# design.net
KiCad netlist of a schematic drawn in Altium Designer
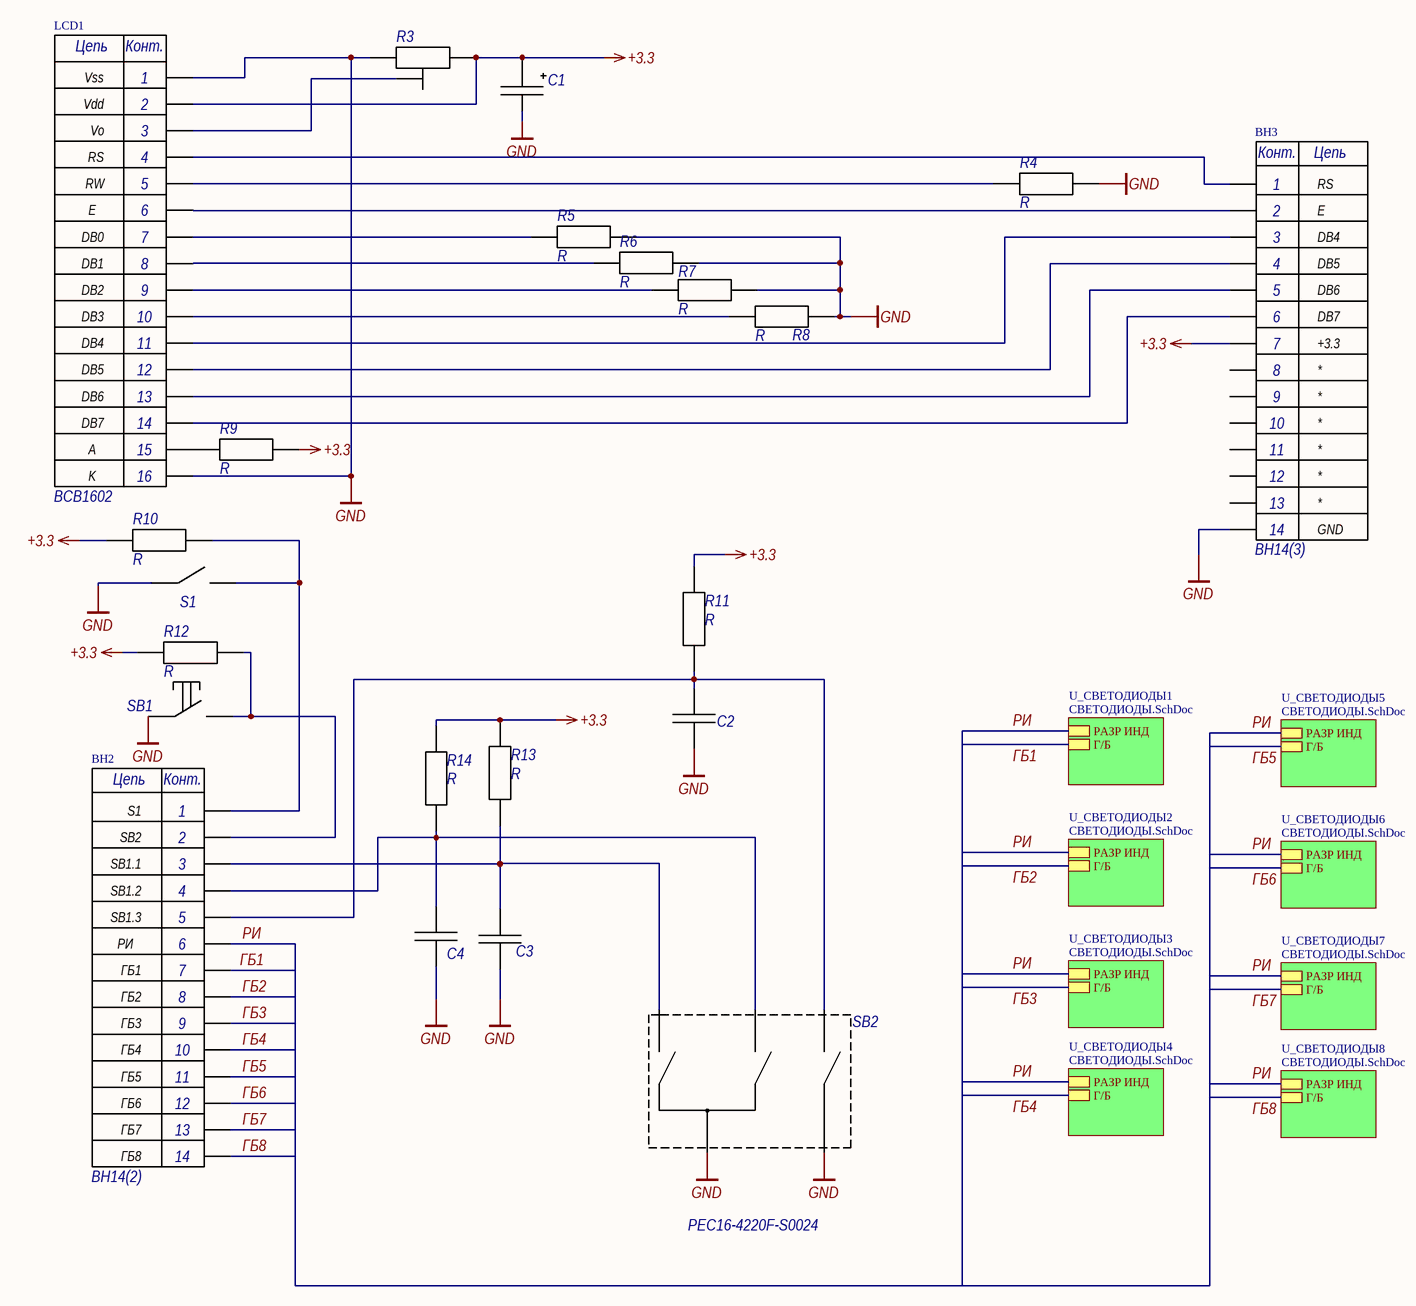
[diagram p0: управление+отладка.SchDoc]

(export (version "E")
  (design (tool "Eeschema 10.0.6"))
  (components
    (comp (ref "BH2")
      (value "BH14(2)")
      (footprint "BH-14 (DS1013-14S) (IDC-14MS)")
      (libsource (lib "UGO") (part "BH14(2)"))
    )
    (comp (ref "BH3")
      (value "BH14(3)")
      (footprint "BH-14 (DS1013-14S) (IDC-14MS)")
      (libsource (lib "UGO") (part "BH14(3)"))
    )
    (comp (ref "C1") (value "C(AlEL)") (footprint "C(AlEL)") (libsource (lib "UGO") (part "C(AlEL)")))
    (comp (ref "C2")
      (value "C(ceramic)")
      (footprint "C(ceramic)")
      (libsource (lib "UGO") (part "C(ceramic)"))
    )
    (comp (ref "C3")
      (value "C(ceramic)")
      (footprint "C(ceramic)")
      (libsource (lib "UGO") (part "C(ceramic)"))
    )
    (comp (ref "C4")
      (value "C(ceramic)")
      (footprint "C(ceramic)")
      (libsource (lib "UGO") (part "C(ceramic)"))
    )
    (comp (ref "LCD1") (value "BCB1602") (footprint "BCB1602") (libsource (lib "UGO") (part "BCB1602")))
    (comp (ref "R3") (value "Comment") (footprint "R(подстр)") (libsource (lib "UGO") (part "R(подстр)")))
    (comp (ref "R4") (value "R") (footprint "R") (libsource (lib "UGO") (part "R")))
    (comp (ref "R5") (value "R") (footprint "R") (libsource (lib "UGO") (part "R")))
    (comp (ref "R6") (value "R") (footprint "R") (libsource (lib "UGO") (part "R")))
    (comp (ref "R7") (value "R") (footprint "R") (libsource (lib "UGO") (part "R")))
    (comp (ref "R8") (value "R") (footprint "R") (libsource (lib "UGO") (part "R")))
    (comp (ref "R9") (value "R") (footprint "R") (libsource (lib "UGO") (part "R")))
    (comp (ref "R10") (value "R") (footprint "R") (libsource (lib "UGO") (part "R")))
    (comp (ref "R11") (value "R") (footprint "R") (libsource (lib "") (part "R_1")))
    (comp (ref "R12") (value "R") (footprint "R") (libsource (lib "UGO") (part "R")))
    (comp (ref "R13") (value "R") (footprint "R") (libsource (lib "") (part "R_1")))
    (comp (ref "R14") (value "R") (footprint "R") (libsource (lib "") (part "R_1")))
    (comp (ref "S1") (value "(?)тумблер") (footprint "MTS-2") (libsource (lib "UGO") (part "(?)тумблер")))
    (comp (ref "SB1") (value "ПУСК") (footprint "кнопка") (libsource (lib "UGO") (part "кнопка")))
    (comp (ref "SB2")
      (value "PEC16-4220F-S0024")
      (footprint "PEC16-4220F-S0024")
      (libsource (lib "UGO") (part "PEC16-4220F-S0024"))
    )
  )
  (nets
    (net (code "1") (name "+3.3") (class "Default")
      (node (ref "BH3") (pin "7") (pinfunction "+3.3_7") (pintype "passive"))
      (node (ref "C1") (pin "1") (pintype "passive"))
      (node (ref "LCD1") (pin "2") (pinfunction "Vdd_2") (pintype "passive"))
      (node (ref "R10") (pin "1") (pintype "passive"))
      (node (ref "R11") (pin "2") (pintype "passive"))
      (node (ref "R12") (pin "1") (pintype "passive"))
      (node (ref "R13") (pin "2") (pintype "passive"))
      (node (ref "R14") (pin "2") (pintype "passive"))
      (node (ref "R3") (pin "1") (pintype "passive"))
      (node (ref "R9") (pin "2") (pintype "passive"))
    )
    (net (code "2") (name "/ГБ1") (class "Default")
      (node (ref "BH2") (pin "7") (pinfunction "ГБ1_7") (pintype "passive"))
    )
    (net (code "3") (name "/ГБ2") (class "Default")
      (node (ref "BH2") (pin "8") (pinfunction "ГБ2_8") (pintype "passive"))
    )
    (net (code "4") (name "/ГБ3") (class "Default")
      (node (ref "BH2") (pin "9") (pinfunction "ГБ3_9") (pintype "passive"))
    )
    (net (code "5") (name "/ГБ4") (class "Default")
      (node (ref "BH2") (pin "10") (pinfunction "ГБ4_10") (pintype "passive"))
    )
    (net (code "6") (name "/ГБ5") (class "Default")
      (node (ref "BH2") (pin "11") (pinfunction "ГБ5_11") (pintype "passive"))
    )
    (net (code "7") (name "/ГБ6") (class "Default")
      (node (ref "BH2") (pin "12") (pinfunction "ГБ6_12") (pintype "passive"))
    )
    (net (code "8") (name "/ГБ7") (class "Default")
      (node (ref "BH2") (pin "13") (pinfunction "ГБ7_13") (pintype "passive"))
    )
    (net (code "9") (name "/ГБ8") (class "Default")
      (node (ref "BH2") (pin "14") (pinfunction "ГБ8_14") (pintype "passive"))
    )
    (net (code "10") (name "/РИ") (class "Default")
      (node (ref "BH2") (pin "6") (pinfunction "РИ_6") (pintype "passive"))
    )
    (net (code "11") (name "GND") (class "Default")
      (node (ref "BH3") (pin "14") (pinfunction "GND_14") (pintype "passive"))
      (node (ref "C1") (pin "2") (pintype "passive"))
      (node (ref "C2") (pin "1") (pintype "passive"))
      (node (ref "C3") (pin "1") (pintype "passive"))
      (node (ref "C4") (pin "1") (pintype "passive"))
      (node (ref "LCD1") (pin "1") (pinfunction "Vss_1") (pintype "passive"))
      (node (ref "LCD1") (pin "16") (pinfunction "K_16") (pintype "passive"))
      (node (ref "R3") (pin "2") (pintype "passive"))
      (node (ref "R4") (pin "2") (pintype "passive"))
      (node (ref "R5") (pin "2") (pintype "passive"))
      (node (ref "R6") (pin "2") (pintype "passive"))
      (node (ref "R7") (pin "2") (pintype "passive"))
      (node (ref "R8") (pin "2") (pintype "passive"))
      (node (ref "S1") (pin "1") (pintype "passive"))
      (node (ref "SB1") (pin "1") (pintype "passive"))
      (node (ref "SB2") (pin "2") (pintype "passive"))
      (node (ref "SB2") (pin "4") (pintype "passive"))
    )
    (net (code "12") (name "Net-(BH2-S1)") (class "Default")
      (node (ref "BH2") (pin "1") (pinfunction "S1_1") (pintype "passive"))
      (node (ref "R10") (pin "2") (pintype "passive"))
      (node (ref "S1") (pin "2") (pintype "passive"))
    )
    (net (code "13") (name "Net-(BH2-SB1.1)") (class "Default")
      (node (ref "BH2") (pin "3") (pinfunction "SB1.1_3") (pintype "passive"))
      (node (ref "C3") (pin "2") (pintype "passive"))
      (node (ref "R13") (pin "1") (pintype "passive"))
      (node (ref "SB2") (pin "1") (pintype "passive"))
    )
    (net (code "14") (name "Net-(BH2-SB1.2)") (class "Default")
      (node (ref "BH2") (pin "4") (pinfunction "SB1.2_4") (pintype "passive"))
      (node (ref "C4") (pin "2") (pintype "passive"))
      (node (ref "R14") (pin "1") (pintype "passive"))
      (node (ref "SB2") (pin "3") (pintype "passive"))
    )
    (net (code "15") (name "Net-(BH2-SB1.3)") (class "Default")
      (node (ref "BH2") (pin "5") (pinfunction "SB1.3_5") (pintype "passive"))
      (node (ref "C2") (pin "2") (pintype "passive"))
      (node (ref "R11") (pin "1") (pintype "passive"))
      (node (ref "SB2") (pin "5") (pintype "passive"))
    )
    (net (code "16") (name "Net-(BH2-SB2)") (class "Default")
      (node (ref "BH2") (pin "2") (pinfunction "SB2_2") (pintype "passive"))
      (node (ref "R12") (pin "2") (pintype "passive"))
      (node (ref "SB1") (pin "2") (pintype "passive"))
    )
    (net (code "17") (name "Net-(BH3-DB4)") (class "Default")
      (node (ref "BH3") (pin "3") (pinfunction "DB4_3") (pintype "passive"))
      (node (ref "LCD1") (pin "11") (pinfunction "DB4_11") (pintype "passive"))
    )
    (net (code "18") (name "Net-(BH3-DB5)") (class "Default")
      (node (ref "BH3") (pin "4") (pinfunction "DB5_4") (pintype "passive"))
      (node (ref "LCD1") (pin "12") (pinfunction "DB5_12") (pintype "passive"))
    )
    (net (code "19") (name "Net-(BH3-DB6)") (class "Default")
      (node (ref "BH3") (pin "5") (pinfunction "DB6_5") (pintype "passive"))
      (node (ref "LCD1") (pin "13") (pinfunction "DB6_13") (pintype "passive"))
    )
    (net (code "20") (name "Net-(BH3-DB7)") (class "Default")
      (node (ref "BH3") (pin "6") (pinfunction "DB7_6") (pintype "passive"))
      (node (ref "LCD1") (pin "14") (pinfunction "DB7_14") (pintype "passive"))
    )
    (net (code "21") (name "Net-(BH3-E)") (class "Default")
      (node (ref "BH3") (pin "2") (pinfunction "E_2") (pintype "passive"))
      (node (ref "LCD1") (pin "6") (pinfunction "E_6") (pintype "passive"))
    )
    (net (code "22") (name "Net-(BH3-RS)") (class "Default")
      (node (ref "BH3") (pin "1") (pinfunction "RS_1") (pintype "passive"))
      (node (ref "LCD1") (pin "4") (pinfunction "RS_4") (pintype "passive"))
    )
    (net (code "23") (name "Net-(LCD1-A)") (class "Default")
      (node (ref "LCD1") (pin "15") (pinfunction "A_15") (pintype "passive"))
      (node (ref "R9") (pin "1") (pintype "passive"))
    )
    (net (code "24") (name "Net-(LCD1-DB0)") (class "Default")
      (node (ref "LCD1") (pin "7") (pinfunction "DB0_7") (pintype "passive"))
      (node (ref "R5") (pin "1") (pintype "passive"))
    )
    (net (code "25") (name "Net-(LCD1-DB1)") (class "Default")
      (node (ref "LCD1") (pin "8") (pinfunction "DB1_8") (pintype "passive"))
      (node (ref "R6") (pin "1") (pintype "passive"))
    )
    (net (code "26") (name "Net-(LCD1-DB2)") (class "Default")
      (node (ref "LCD1") (pin "9") (pinfunction "DB2_9") (pintype "passive"))
      (node (ref "R7") (pin "1") (pintype "passive"))
    )
    (net (code "27") (name "Net-(LCD1-DB3)") (class "Default")
      (node (ref "LCD1") (pin "10") (pinfunction "DB3_10") (pintype "passive"))
      (node (ref "R8") (pin "1") (pintype "passive"))
    )
    (net (code "28") (name "Net-(LCD1-RW)") (class "Default")
      (node (ref "LCD1") (pin "5") (pinfunction "RW_5") (pintype "passive"))
      (node (ref "R4") (pin "1") (pintype "passive"))
    )
    (net (code "29") (name "Net-(LCD1-Vo)") (class "Default")
      (node (ref "LCD1") (pin "3") (pinfunction "Vo_3") (pintype "passive"))
      (node (ref "R3") (pin "3") (pintype "passive"))
    )
    (net (code "30") (name "unconnected-(BH3-*-Pad8)") (class "Default")
      (node (ref "BH3") (pin "8") (pinfunction "*_8") (pintype "passive"))
    )
    (net (code "31") (name "unconnected-(BH3-*-Pad9)") (class "Default")
      (node (ref "BH3") (pin "9") (pinfunction "*_9") (pintype "passive"))
    )
    (net (code "32") (name "unconnected-(BH3-*-Pad10)") (class "Default")
      (node (ref "BH3") (pin "10") (pinfunction "*_10") (pintype "passive"))
    )
    (net (code "33") (name "unconnected-(BH3-*-Pad11)") (class "Default")
      (node (ref "BH3") (pin "11") (pinfunction "*_11") (pintype "passive"))
    )
    (net (code "34") (name "unconnected-(BH3-*-Pad12)") (class "Default")
      (node (ref "BH3") (pin "12") (pinfunction "*_12") (pintype "passive"))
    )
    (net (code "35") (name "unconnected-(BH3-*-Pad13)") (class "Default")
      (node (ref "BH3") (pin "13") (pinfunction "*_13") (pintype "passive"))
    )
  )
)
